# Placa_principal.net
KiCad netlist of a schematic drawn in EAGLE
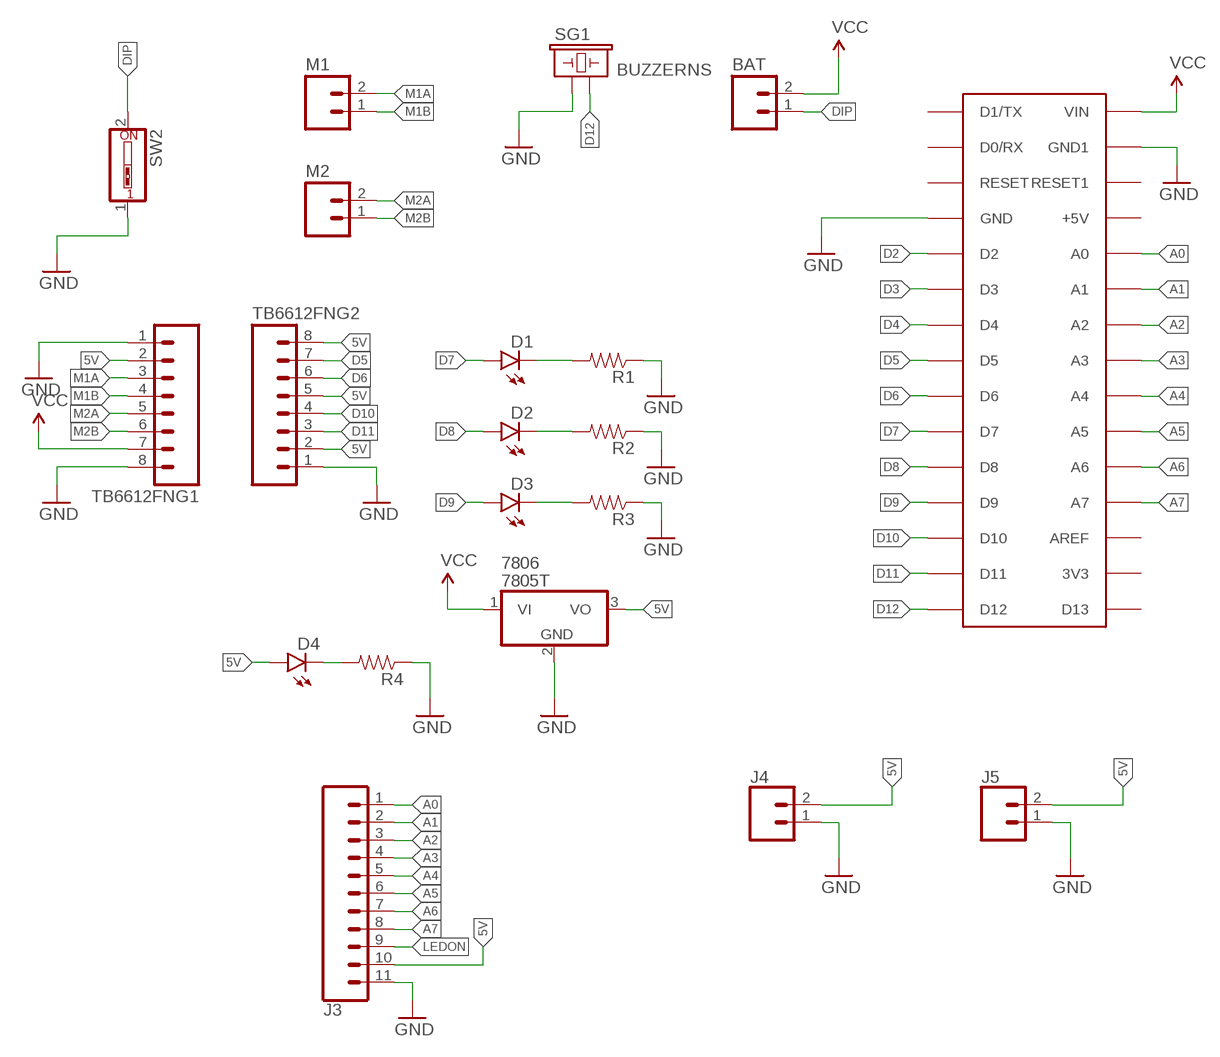
[diagram p0: schematic, sheet 1]

(export (version "E")
  (design (tool "Eeschema 10.0.6"))
  (components
    (comp (ref "7806")
      (value "7805T")
      (footprint "eagle-import:TO220H")
      (libsource (lib "eagle-import") (part "78T05"))
    )
    (comp (ref "BAT")
      (value "M02PTH")
      (footprint "eagle-import:1X02@1")
      (libsource (lib "eagle-import") (part "M02PTH"))
    )
    (comp (ref "D1")
      (value "LED5MM")
      (footprint "eagle-import:LED5MM")
      (libsource (lib "eagle-import") (part "LED5MM"))
    )
    (comp (ref "D2")
      (value "LED5MM")
      (footprint "eagle-import:LED5MM")
      (libsource (lib "eagle-import") (part "LED5MM"))
    )
    (comp (ref "D3")
      (value "LED5MM")
      (footprint "eagle-import:LED5MM")
      (libsource (lib "eagle-import") (part "LED5MM"))
    )
    (comp (ref "D4")
      (value "LED5MM")
      (footprint "eagle-import:LED5MM")
      (libsource (lib "eagle-import") (part "LED5MM"))
    )
    (comp (ref "J3")
      (value "CONN_11")
      (footprint "eagle-import:1X11")
      (libsource (lib "eagle-import") (part "CONN_11"))
    )
    (comp (ref "J4")
      (value "CONN_02")
      (footprint "eagle-import:1X02")
      (libsource (lib "eagle-import") (part "CONN_02"))
    )
    (comp (ref "J5")
      (value "CONN_02")
      (footprint "eagle-import:1X02")
      (libsource (lib "eagle-import") (part "CONN_02"))
    )
    (comp (ref "M1")
      (value "M02JST-PTH-VERT")
      (footprint "eagle-import:JST-2-PTH-VERT")
      (libsource (lib "eagle-import") (part "M02JST-PTH-VERT"))
    )
    (comp (ref "M2")
      (value "M02JST-PTH-VERT")
      (footprint "eagle-import:JST-2-PTH-VERT")
      (libsource (lib "eagle-import") (part "M02JST-PTH-VERT"))
    )
    (comp (ref "R1")
      (value "RESISTOREZ")
      (footprint "eagle-import:AXIAL-0.3EZ")
      (libsource (lib "eagle-import") (part "RESISTOREZ"))
    )
    (comp (ref "R2")
      (value "RESISTOREZ")
      (footprint "eagle-import:AXIAL-0.3EZ")
      (libsource (lib "eagle-import") (part "RESISTOREZ"))
    )
    (comp (ref "R3")
      (value "RESISTOREZ")
      (footprint "eagle-import:AXIAL-0.3EZ")
      (libsource (lib "eagle-import") (part "RESISTOREZ"))
    )
    (comp (ref "R4")
      (value "RESISTOREZ")
      (footprint "eagle-import:AXIAL-0.3EZ")
      (libsource (lib "eagle-import") (part "RESISTOREZ"))
    )
    (comp (ref "SG1")
      (value "BUZZERNS")
      (footprint "eagle-import:BUZZER-12MM-NS")
      (libsource (lib "eagle-import") (part "BUZZERNS"))
    )
    (comp (ref "SW2")
      (value "SW_DIP-1")
      (footprint "eagle-import:EDG-01")
      (libsource (lib "eagle-import") (part "SW_DIP-1"))
    )
    (comp (ref "TB6612FNG1")
      (value "M08")
      (footprint "eagle-import:1X08_ROUND")
      (libsource (lib "eagle-import") (part "M08"))
    )
    (comp (ref "TB6612FNG2")
      (value "M08")
      (footprint "eagle-import:1X08_ROUND")
      (libsource (lib "eagle-import") (part "M08"))
    )
    (comp (ref "U1")
      (value "NANO")
      (footprint "eagle-import:PDIP-32")
      (libsource (lib "eagle-import") (part "ARDUINONANO"))
    )
  )
  (nets
    (net (code "1") (name "5V") (class "Default")
      (node (ref "7806") (pin "3") (pinfunction "VO_3") (pintype "passive"))
      (node (ref "D4") (pin "A") (pinfunction "A_A") (pintype "passive"))
      (node (ref "J3") (pin "10") (pinfunction "10_10") (pintype "passive"))
      (node (ref "J4") (pin "2") (pinfunction "2_2") (pintype "passive"))
      (node (ref "J5") (pin "2") (pinfunction "2_2") (pintype "passive"))
      (node (ref "TB6612FNG1") (pin "2") (pinfunction "2_2") (pintype "passive"))
      (node (ref "TB6612FNG2") (pin "2") (pinfunction "2_2") (pintype "passive"))
      (node (ref "TB6612FNG2") (pin "5") (pinfunction "5_5") (pintype "passive"))
      (node (ref "TB6612FNG2") (pin "8") (pinfunction "8_8") (pintype "passive"))
    )
    (net (code "2") (name "A0") (class "Default")
      (node (ref "J3") (pin "1") (pinfunction "1_1") (pintype "passive"))
      (node (ref "U1") (pin "A0") (pinfunction "A0_A0") (pintype "bidirectional"))
    )
    (net (code "3") (name "A1") (class "Default")
      (node (ref "J3") (pin "2") (pinfunction "2_2") (pintype "passive"))
      (node (ref "U1") (pin "A1") (pinfunction "A1_A1") (pintype "bidirectional"))
    )
    (net (code "4") (name "A2") (class "Default")
      (node (ref "J3") (pin "3") (pinfunction "3_3") (pintype "passive"))
      (node (ref "U1") (pin "A2") (pinfunction "A2_A2") (pintype "bidirectional"))
    )
    (net (code "5") (name "A3") (class "Default")
      (node (ref "J3") (pin "4") (pinfunction "4_4") (pintype "passive"))
      (node (ref "U1") (pin "A3") (pinfunction "A3_A3") (pintype "bidirectional"))
    )
    (net (code "6") (name "A4") (class "Default")
      (node (ref "J3") (pin "5") (pinfunction "5_5") (pintype "passive"))
      (node (ref "U1") (pin "A4") (pinfunction "A4_A4") (pintype "bidirectional"))
    )
    (net (code "7") (name "A5") (class "Default")
      (node (ref "J3") (pin "6") (pinfunction "6_6") (pintype "passive"))
      (node (ref "U1") (pin "A5") (pinfunction "A5_A5") (pintype "bidirectional"))
    )
    (net (code "8") (name "A6") (class "Default")
      (node (ref "J3") (pin "7") (pinfunction "7_7") (pintype "passive"))
      (node (ref "U1") (pin "A6") (pinfunction "A6_A6") (pintype "bidirectional"))
    )
    (net (code "9") (name "A7") (class "Default")
      (node (ref "J3") (pin "8") (pinfunction "8_8") (pintype "passive"))
      (node (ref "U1") (pin "A7") (pinfunction "A7_A7") (pintype "bidirectional"))
    )
    (net (code "10") (name "D2") (class "Default")
      (node (ref "U1") (pin "D2") (pinfunction "D2_D2") (pintype "bidirectional"))
    )
    (net (code "11") (name "D3") (class "Default")
      (node (ref "U1") (pin "D3") (pinfunction "D3_D3") (pintype "bidirectional"))
    )
    (net (code "12") (name "D4") (class "Default")
      (node (ref "U1") (pin "D4") (pinfunction "D4_D4") (pintype "bidirectional"))
    )
    (net (code "13") (name "D5") (class "Default")
      (node (ref "TB6612FNG2") (pin "7") (pinfunction "7_7") (pintype "passive"))
      (node (ref "U1") (pin "D5") (pinfunction "D5_D5") (pintype "bidirectional"))
    )
    (net (code "14") (name "D6") (class "Default")
      (node (ref "TB6612FNG2") (pin "6") (pinfunction "6_6") (pintype "passive"))
      (node (ref "U1") (pin "D6") (pinfunction "D6_D6") (pintype "bidirectional"))
    )
    (net (code "15") (name "D7") (class "Default")
      (node (ref "D1") (pin "A") (pinfunction "A_A") (pintype "passive"))
      (node (ref "U1") (pin "D7") (pinfunction "D7_D7") (pintype "bidirectional"))
    )
    (net (code "16") (name "D8") (class "Default")
      (node (ref "D2") (pin "A") (pinfunction "A_A") (pintype "passive"))
      (node (ref "U1") (pin "D8") (pinfunction "D8_D8") (pintype "bidirectional"))
    )
    (net (code "17") (name "D9") (class "Default")
      (node (ref "D3") (pin "A") (pinfunction "A_A") (pintype "passive"))
      (node (ref "U1") (pin "D9") (pinfunction "D9_D9") (pintype "bidirectional"))
    )
    (net (code "18") (name "D10") (class "Default")
      (node (ref "TB6612FNG2") (pin "4") (pinfunction "4_4") (pintype "passive"))
      (node (ref "U1") (pin "D10") (pinfunction "D10_D10") (pintype "bidirectional"))
    )
    (net (code "19") (name "D11") (class "Default")
      (node (ref "TB6612FNG2") (pin "3") (pinfunction "3_3") (pintype "passive"))
      (node (ref "U1") (pin "D11") (pinfunction "D11_D11") (pintype "bidirectional"))
    )
    (net (code "20") (name "D12") (class "Default")
      (node (ref "SG1") (pin "-") (pinfunction "2_-") (pintype "passive"))
      (node (ref "U1") (pin "D12") (pinfunction "D12_D12") (pintype "bidirectional"))
    )
    (net (code "21") (name "DIP") (class "Default")
      (node (ref "BAT") (pin "1") (pinfunction "1_1") (pintype "passive"))
      (node (ref "SW2") (pin "2") (pinfunction "2_2") (pintype "passive"))
    )
    (net (code "22") (name "GND") (class "Default")
      (node (ref "7806") (pin "2") (pinfunction "GND_2") (pintype "passive"))
      (node (ref "J3") (pin "11") (pinfunction "11_11") (pintype "passive"))
      (node (ref "J4") (pin "1") (pinfunction "1_1") (pintype "passive"))
      (node (ref "J5") (pin "1") (pinfunction "1_1") (pintype "passive"))
      (node (ref "R1") (pin "P$1") (pinfunction "1_P$1") (pintype "passive"))
      (node (ref "R2") (pin "P$1") (pinfunction "1_P$1") (pintype "passive"))
      (node (ref "R3") (pin "P$1") (pinfunction "1_P$1") (pintype "passive"))
      (node (ref "R4") (pin "P$1") (pinfunction "1_P$1") (pintype "passive"))
      (node (ref "SG1") (pin "+") (pinfunction "1_+") (pintype "passive"))
      (node (ref "SW2") (pin "1") (pinfunction "1_1") (pintype "passive"))
      (node (ref "TB6612FNG1") (pin "1") (pinfunction "1_1") (pintype "passive"))
      (node (ref "TB6612FNG1") (pin "8") (pinfunction "8_8") (pintype "passive"))
      (node (ref "TB6612FNG2") (pin "1") (pinfunction "1_1") (pintype "passive"))
      (node (ref "U1") (pin "GND") (pinfunction "GND_GND") (pintype "bidirectional"))
      (node (ref "U1") (pin "GND1") (pinfunction "GND1_GND1") (pintype "bidirectional"))
    )
    (net (code "23") (name "LEDON") (class "Default")
      (node (ref "J3") (pin "9") (pinfunction "9_9") (pintype "passive"))
    )
    (net (code "24") (name "M1A") (class "Default")
      (node (ref "M1") (pin "2") (pinfunction "2_2") (pintype "passive"))
      (node (ref "TB6612FNG1") (pin "3") (pinfunction "3_3") (pintype "passive"))
    )
    (net (code "25") (name "M1B") (class "Default")
      (node (ref "M1") (pin "1") (pinfunction "1_1") (pintype "passive"))
      (node (ref "TB6612FNG1") (pin "4") (pinfunction "4_4") (pintype "passive"))
    )
    (net (code "26") (name "M2A") (class "Default")
      (node (ref "M2") (pin "2") (pinfunction "2_2") (pintype "passive"))
      (node (ref "TB6612FNG1") (pin "5") (pinfunction "5_5") (pintype "passive"))
    )
    (net (code "27") (name "M2B") (class "Default")
      (node (ref "M2") (pin "1") (pinfunction "1_1") (pintype "passive"))
      (node (ref "TB6612FNG1") (pin "6") (pinfunction "6_6") (pintype "passive"))
    )
    (net (code "28") (name "Net-(D1-C)") (class "Default")
      (node (ref "D1") (pin "K") (pinfunction "C_K") (pintype "passive"))
      (node (ref "R1") (pin "P$2") (pinfunction "2_P$2") (pintype "passive"))
    )
    (net (code "29") (name "Net-(D2-C)") (class "Default")
      (node (ref "D2") (pin "K") (pinfunction "C_K") (pintype "passive"))
      (node (ref "R2") (pin "P$2") (pinfunction "2_P$2") (pintype "passive"))
    )
    (net (code "30") (name "Net-(D3-C)") (class "Default")
      (node (ref "D3") (pin "K") (pinfunction "C_K") (pintype "passive"))
      (node (ref "R3") (pin "P$2") (pinfunction "2_P$2") (pintype "passive"))
    )
    (net (code "31") (name "Net-(D4-C)") (class "Default")
      (node (ref "D4") (pin "K") (pinfunction "C_K") (pintype "passive"))
      (node (ref "R4") (pin "P$2") (pinfunction "2_P$2") (pintype "passive"))
    )
    (net (code "32") (name "VCC") (class "Default")
      (node (ref "7806") (pin "1") (pinfunction "VI_1") (pintype "input"))
      (node (ref "BAT") (pin "2") (pinfunction "2_2") (pintype "passive"))
      (node (ref "TB6612FNG1") (pin "7") (pinfunction "7_7") (pintype "passive"))
      (node (ref "U1") (pin "VIN") (pinfunction "VIN_VIN") (pintype "bidirectional"))
    )
    (net (code "33") (name "unconnected-(U1-Pad+5V)") (class "Default")
      (node (ref "U1") (pin "+5V") (pinfunction "+5V_+5V") (pintype "bidirectional"))
    )
    (net (code "34") (name "unconnected-(U1-Pad3V3)") (class "Default")
      (node (ref "U1") (pin "3V3") (pinfunction "3V3_3V3") (pintype "bidirectional"))
    )
    (net (code "35") (name "unconnected-(U1-PadAREF)") (class "Default")
      (node (ref "U1") (pin "AREF") (pinfunction "AREF_AREF") (pintype "bidirectional"))
    )
    (net (code "36") (name "unconnected-(U1-PadD0{slash}RX)") (class "Default")
      (node (ref "U1") (pin "D0/RX") (pinfunction "D0/RX_D0/RX") (pintype "bidirectional"))
    )
    (net (code "37") (name "unconnected-(U1-PadD1{slash}TX)") (class "Default")
      (node (ref "U1") (pin "D1/TX") (pinfunction "D1/TX_D1/TX") (pintype "bidirectional"))
    )
    (net (code "38") (name "unconnected-(U1-PadD13)") (class "Default")
      (node (ref "U1") (pin "D13") (pinfunction "D13_D13") (pintype "bidirectional"))
    )
    (net (code "39") (name "unconnected-(U1-PadRESET)") (class "Default")
      (node (ref "U1") (pin "RESET") (pinfunction "RESET_RESET") (pintype "bidirectional"))
    )
    (net (code "40") (name "unconnected-(U1-PadRESET1)") (class "Default")
      (node (ref "U1") (pin "RESET1") (pinfunction "RESET1_RESET1") (pintype "bidirectional"))
    )
  )
)
